# SHDN-IMD-S03-V00-Shutdown.net
KiCad netlist of a schematic drawn in Altium Designer
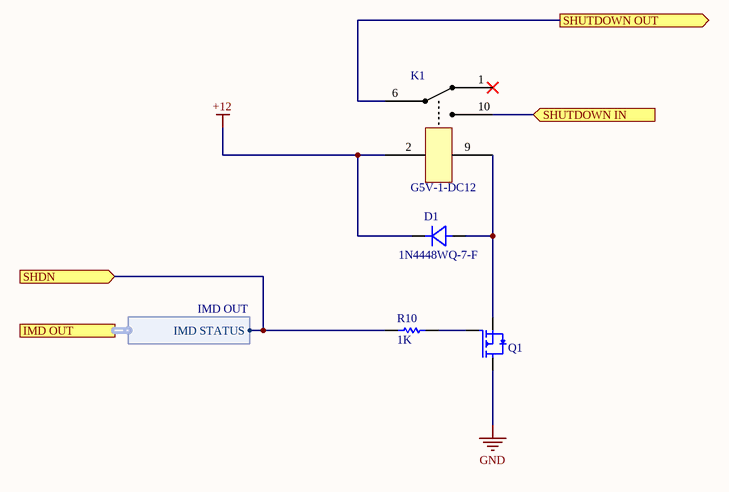
[diagram p0: SHDN-IMD-S03-V00-Shutdown.SchDoc]

(export (version "E")
  (design (tool "Eeschema 10.0.6"))
  (components
    (comp (ref "D1")
      (value "1N4448WQ-7-F")
      (footprint "SMA")
      (description "Diode, SMD, 75V, 5%, 250mA, SOD123")
      (fields
        (field (name "MANUFACTURER") "ON Semiconductor / Fairchild")
        (field (name "MANUFACTURER PART NUMBER") "1N914BWS")
      )
      (libsource (lib "QUTMS_DiodeLibrary") (part "1N4448WQ-7-F"))
    )
    (comp (ref "K1")
      (value "G5V-1-DC12")
      (footprint "G5V-1")
      (description "General Purpose Relay SPDT (1 Form C) Through Hole, 12V, 2A")
      (libsource (lib "QUTMS_RelayLibrary") (part "G5V-1-DC12"))
    )
    (comp (ref "Q1")
      (value "~")
      (footprint "PMV15UNEAR")
      (description "MOSFET N-CH, 20V, SOT23")
      (fields (field (name "MANUFACTURER") "Nexperia"))
      (libsource (lib "CellMonitor") (part "PMV15UNEAR"))
    )
    (comp (ref "R10")
      (value "1K")
      (footprint "Res_ThinFilm_0603")
      (description "Resistor, SMD, 1k, 0.1W, 5%, 0603")
      (libsource (lib "StandardResistors") (part "1k 5% 0603"))
    )
  )
  (nets
    (net (code "3") (name "+12") (class "Default")
      (node (ref "D1") (pin "K") (pinfunction "Cathode_K") (pintype "passive"))
      (node (ref "K1") (pin "2") (pinfunction "2_2") (pintype "passive"))
    )
    (net (code "4") (name "/SHDN") (class "Default")
      (node (ref "R10") (pin "1") (pinfunction "1_1") (pintype "passive"))
    )
    (net (code "5") (name "/SHUTDOWN IN") (class "Default")
      (node (ref "K1") (pin "10") (pinfunction "10_10") (pintype "passive"))
    )
    (net (code "6") (name "/SHUTDOWN OUT") (class "Default")
      (node (ref "K1") (pin "6") (pinfunction "6_6") (pintype "passive"))
    )
    (net (code "8") (name "GND") (class "Default")
      (node (ref "Q1") (pin "D") (pinfunction "Drain_D") (pintype "passive"))
    )
    (net (code "9") (name "Net-(D1-Anode)") (class "Default")
      (node (ref "D1") (pin "A") (pinfunction "Anode_A") (pintype "passive"))
      (node (ref "K1") (pin "9") (pinfunction "9_9") (pintype "passive"))
      (node (ref "Q1") (pin "S") (pinfunction "Source_S") (pintype "passive"))
    )
    (net (code "10") (name "Net-(Q1-Gate)") (class "Default")
      (node (ref "Q1") (pin "G") (pinfunction "Gate_G") (pintype "passive"))
      (node (ref "R10") (pin "2") (pinfunction "2_2") (pintype "passive"))
    )
    (net (code "11") (name "unconnected-(K1-Pad1)") (class "Default")
      (node (ref "K1") (pin "1") (pinfunction "1_1") (pintype "passive+no_connect"))
    )
  )
)
